# PWR.net
KiCad netlist of a schematic drawn in Altium Designer
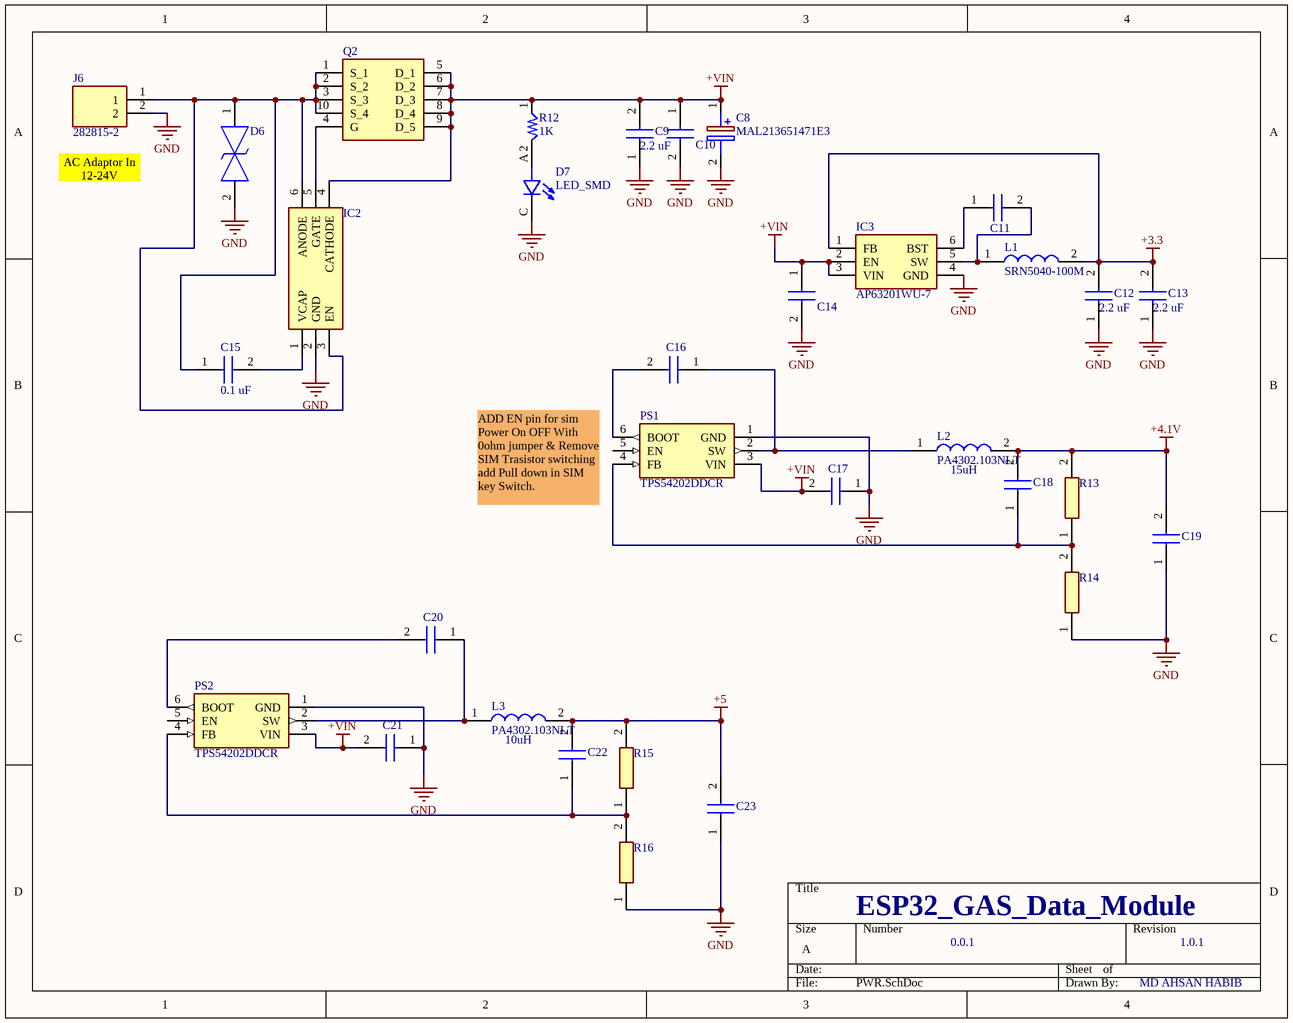
[diagram p0: PWR.SchDoc]

(export (version "E")
  (design (tool "Eeschema 10.0.6"))
  (components
    (comp (ref "C8")
      (value "MAL213651471E3")
      (footprint "CAPPRD500W60D1300H2700")
      (description "Capacitor Polarised")
      (fields (field (name "MOUSER PART NUMBER") "594-2222-136-51471"))
      (libsource (lib "Valve_Controller_Lib") (part "MAL213651471E3"))
    )
    (comp (ref "C9")
      (value "2.2 uF")
      (footprint "CAP0603")
      (description "Capacitor")
      (fields
        (field (name "MANUFACTURER_PART_NUMBER") "CC0603KRX7R9BB104")
        (field (name "MOUSER PART NUMBER") "603-CC603KRX7R9BB104")
      )
      (libsource (lib "Valve_Controller_Lib") (part "CC0603KRX7R9BB104"))
    )
    (comp (ref "C10")
      (value "C5750X5R1H106K230KA")
      (footprint "C5750_Commercial")
      (description "Capacitor")
      (fields (field (name "MOUSER PART NUMBER") "810-C5750X5R1H106K"))
      (libsource (lib "Valve_Controller_Lib") (part "C5750X5R1H106K230KA"))
    )
    (comp (ref "C11")
      (value "C0805C104M5RAC-TU")
      (footprint "CAP0603")
      (description "Capacitor")
      (libsource (lib "Valve_Controller_Lib") (part "C0805C104M5RAC-TU"))
    )
    (comp (ref "C12")
      (value "2.2 uF")
      (footprint "CAP0603")
      (description "Capacitor")
      (fields
        (field (name "MANUFACTURER_PART_NUMBER") "CC0603KRX7R9BB104")
        (field (name "MOUSER PART NUMBER") "603-CC603KRX7R9BB104")
      )
      (libsource (lib "Valve_Controller_Lib") (part "CC0603KRX7R9BB104"))
    )
    (comp (ref "C13")
      (value "2.2 uF")
      (footprint "CAP0603")
      (description "Capacitor")
      (fields
        (field (name "MANUFACTURER_PART_NUMBER") "CC0603KRX7R9BB104")
        (field (name "MOUSER PART NUMBER") "603-CC603KRX7R9BB104")
      )
      (libsource (lib "Valve_Controller_Lib") (part "CC0603KRX7R9BB104"))
    )
    (comp (ref "C14")
      (value "C5750X5R1H106K230KA")
      (footprint "CAP0603")
      (description "Capacitor")
      (fields (field (name "MOUSER PART NUMBER") "810-C5750X5R1H106K"))
      (libsource (lib "Valve_Controller_Lib") (part "C5750X5R1H106K230KA"))
    )
    (comp (ref "C15")
      (value "0.1 uF")
      (footprint "CAP0603")
      (description "Capacitor")
      (fields
        (field (name "MANUFACTURER_PART_NUMBER") "CC0603KRX7R9BB104")
        (field (name "MOUSER PART NUMBER") "603-CC603KRX7R9BB104")
      )
      (libsource (lib "Valve_Controller_Lib") (part "CC0603KRX7R9BB104"))
    )
    (comp (ref "C16")
      (value "C0805C104M5RAC-TU")
      (footprint "CAPC2012X88N")
      (description "Capacitor")
      (libsource (lib "Valve_Controller_Lib") (part "C0805C104M5RAC-TU"))
    )
    (comp (ref "C17")
      (value "C5750X5R1H106K230KA")
      (footprint "CAP0603")
      (description "Capacitor")
      (fields (field (name "MOUSER PART NUMBER") "810-C5750X5R1H106K"))
      (libsource (lib "Valve_Controller_Lib") (part "C5750X5R1H106K230KA"))
    )
    (comp (ref "C18")
      (value "GRM0335C1E560JA01D")
      (footprint "CAP0603")
      (description "Capacitor")
      (fields (field (name "MOUSER PART NUMBER") "81-GRM0335C1E560JA1D"))
      (libsource (lib "Valve_Controller_Lib") (part "GRM0335C1E560JA01D"))
    )
    (comp (ref "C19")
      (value "GRM32ER61C476KE15L")
      (footprint "CAPC3225X270N")
      (description "Capacitor")
      (fields (field (name "MOUSER PART NUMBER") "81-GRM32ER61C476KE5L"))
      (libsource (lib "Valve_Controller_Lib") (part "GRM32ER61C476KE15L"))
    )
    (comp (ref "C20")
      (value "C0805C104M5RAC-TU")
      (footprint "CAPC2012X88N")
      (description "Capacitor")
      (libsource (lib "Valve_Controller_Lib") (part "C0805C104M5RAC-TU"))
    )
    (comp (ref "C21")
      (value "C5750X5R1H106K230KA")
      (footprint "CAP0603")
      (description "Capacitor")
      (fields (field (name "MOUSER PART NUMBER") "810-C5750X5R1H106K"))
      (libsource (lib "Valve_Controller_Lib") (part "C5750X5R1H106K230KA"))
    )
    (comp (ref "C22")
      (value "CGA1A2C0G1E820J030BA")
      (footprint "CAP0603")
      (description "Capacitor")
      (libsource (lib "*") (part "CGA1A2C0G1E820J030BA"))
    )
    (comp (ref "C23")
      (value "GRM32ER61C476KE15L")
      (footprint "CAPC3225X270N")
      (description "Capacitor")
      (fields (field (name "MOUSER PART NUMBER") "81-GRM32ER61C476KE5L"))
      (libsource (lib "Valve_Controller_Lib") (part "GRM32ER61C476KE15L"))
    )
    (comp (ref "D6")
      (value "SMBJ24CA-13-F")
      (footprint "SamacSys:DIONM5336X250N")
      (description "TVS Diode (Bi-directional)")
      (fields (field (name "MOUSER PART NUMBER") "621-SMBJ24CA-13-F"))
      (libsource (lib "*") (part "SMBJ24CA-13-F"))
    )
    (comp (ref "D7")
      (value "LED_SMD")
      (footprint "LEDSC125X200X90-2N")
      (description "Red 633nm LED Indication - Discrete 2.1V 0805 (2012 Metric)")
      (fields (field (name "MF") "Dialight") (field (name "MP") "599-0110-007F"))
      (libsource (lib "Valve_Controller_Lib") (part "5990110007F"))
    )
    (comp (ref "IC2")
      (value "LM74700QDBVTQ1")
      (footprint "SamacSys:SOT95P280X145-6N")
      (description "Integrated Circuit")
      (fields (field (name "MANUFACTURER_PART_NUMBER") "LM74700-Q1MKX-1/NOPB"))
      (libsource (lib "*") (part "LM74700-Q1MKX-1_NOPB"))
    )
    (comp (ref "IC3")
      (value "AP63201WU-7")
      (footprint "SamacSys:SOT95P280X100-6N")
      (description "Integrated Circuit")
      (fields (field (name "MOUSER PART NUMBER") "621-AP63201WU-7"))
      (libsource (lib "*") (part "AP63201WU-7"))
    )
    (comp (ref "J6")
      (value "282815-2")
      (footprint "SamacSys:SHDRRA2W102P0X508_1X2_1016X1200X850P")
      (description "Connector")
      (fields (field (name "MOUSER PART NUMBER") "571-282815-2"))
      (libsource (lib "*") (part "282815-2"))
    )
    (comp (ref "L1")
      (value "SRN5040-100M")
      (footprint "SamacSys:SRN5040")
      (description "Inductor")
      (fields (field (name "MOUSER PART NUMBER") "652-SRN5040-100M"))
      (libsource (lib "*") (part "SRN5040-100M"))
    )
    (comp (ref "L2")
      (value "PA4302.103NLT")
      (footprint "SamacSys:PA4302103NLT")
      (description "Inductor")
      (fields (field (name "MOUSER PART NUMBER") "673-PA4302.103NLT"))
      (libsource (lib "*") (part "PA4302.103NLT"))
    )
    (comp (ref "L3")
      (value "PA4302.103NLT")
      (footprint "SamacSys:PA4302103NLT")
      (description "Inductor")
      (fields (field (name "MOUSER PART NUMBER") "673-PA4302.103NLT"))
      (libsource (lib "*") (part "PA4302.103NLT"))
    )
    (comp (ref "PS1")
      (value "TPS54202DDCR")
      (footprint "SOT95P280X110-6N")
      (description "Power Supply")
      (fields (field (name "MOUSER PART NUMBER") "595-TPS54202DDCR"))
      (libsource (lib "Valve_Controller_Lib") (part "TPS54202DDCR"))
    )
    (comp (ref "PS2")
      (value "TPS54202DDCR")
      (footprint "SOT95P280X110-6N")
      (description "Power Supply")
      (fields (field (name "MOUSER PART NUMBER") "595-TPS54202DDCR"))
      (libsource (lib "Valve_Controller_Lib") (part "TPS54202DDCR"))
    )
    (comp (ref "Q2")
      (value "BSC014N06NSATMA1")
      (footprint "BSC010N04LS6ATMA1")
      (description "MOSFET (N-Channel)")
      (fields (field (name "MOUSER PART NUMBER") "726-BSC014N06NSATMA1"))
      (libsource (lib "Valve_Controller_Lib") (part "BSC014N06NSATMA1"))
    )
    (comp (ref "R12")
      (value "1K")
      (footprint "RES0603")
      (description "Resistor")
      (fields (field (name "MANUFACTURER_PART_NUMBER") "0603WAF1001T5E"))
      (libsource (lib "Valve_Controller_Lib") (part "RES"))
    )
    (comp (ref "R13")
      (value "CRCW0402100KFKEDHP")
      (footprint "RES0603")
      (description "Resistor")
      (fields (field (name "MOUSER PART NUMBER") "71-CRCW0402100KFKEDH"))
      (libsource (lib "Valve_Controller_Lib") (part "CRCW0402100KFKEDHP"))
    )
    (comp (ref "R14")
      (value "CRCW040216K9FKEDHP")
      (footprint "RES0603")
      (description "Resistor")
      (fields (field (name "MOUSER PART NUMBER") "71-CRCW040216K9FKEDH"))
      (libsource (lib "Valve_Controller_Lib") (part "CRCW040216K9FKEDHP"))
    )
    (comp (ref "R15")
      (value "CRCW0402100KFKEDHP")
      (footprint "RES0603")
      (description "Resistor")
      (fields (field (name "MOUSER PART NUMBER") "71-CRCW0402100KFKEDH"))
      (libsource (lib "Valve_Controller_Lib") (part "CRCW0402100KFKEDHP"))
    )
    (comp (ref "R16")
      (value "CRCW040213K7FKEDHP")
      (footprint "RES0603")
      (description "Resistor")
      (libsource (lib "*") (part "CRCW040213K7FKEDHP"))
    )
  )
  (nets
    (net (code "1") (name "+3.3") (class "Default")
      (node (ref "C12") (pin "2") (pinfunction "2_2") (pintype "passive"))
      (node (ref "C13") (pin "2") (pinfunction "2_2") (pintype "passive"))
      (node (ref "IC3") (pin "1") (pinfunction "FB_1") (pintype "passive"))
      (node (ref "L1") (pin "2") (pinfunction "2_2") (pintype "passive"))
    )
    (net (code "2") (name "+4.1V") (class "Default")
      (node (ref "C18") (pin "2") (pinfunction "2_2") (pintype "passive"))
      (node (ref "C19") (pin "2") (pinfunction "2_2") (pintype "passive"))
      (node (ref "L2") (pin "2") (pinfunction "2_2") (pintype "passive"))
      (node (ref "R13") (pin "2") (pinfunction "2_2") (pintype "passive"))
    )
    (net (code "3") (name "+5") (class "Default")
      (node (ref "C22") (pin "2") (pinfunction "2_2") (pintype "passive"))
      (node (ref "C23") (pin "2") (pinfunction "2_2") (pintype "passive"))
      (node (ref "L3") (pin "2") (pinfunction "2_2") (pintype "passive"))
      (node (ref "R15") (pin "2") (pinfunction "2_2") (pintype "passive"))
    )
    (net (code "4") (name "+VIN") (class "Default")
      (node (ref "C10") (pin "1") (pinfunction "1_1") (pintype "passive"))
      (node (ref "C14") (pin "1") (pinfunction "1_1") (pintype "passive"))
      (node (ref "C17") (pin "2") (pinfunction "2_2") (pintype "passive"))
      (node (ref "C21") (pin "2") (pinfunction "2_2") (pintype "passive"))
      (node (ref "C8") (pin "1") (pinfunction "+_1") (pintype "passive"))
      (node (ref "C9") (pin "2") (pinfunction "2_2") (pintype "passive"))
      (node (ref "IC2") (pin "4") (pinfunction "CATHODE_4") (pintype "passive"))
      (node (ref "IC3") (pin "2") (pinfunction "EN_2") (pintype "passive"))
      (node (ref "IC3") (pin "3") (pinfunction "VIN_3") (pintype "passive"))
      (node (ref "PS1") (pin "3") (pinfunction "VIN_3") (pintype "power_in"))
      (node (ref "PS2") (pin "3") (pinfunction "VIN_3") (pintype "power_in"))
      (node (ref "Q2") (pin "5") (pinfunction "D_1_5") (pintype "passive"))
      (node (ref "Q2") (pin "6") (pinfunction "D_2_6") (pintype "passive"))
      (node (ref "Q2") (pin "7") (pinfunction "D_3_7") (pintype "passive"))
      (node (ref "Q2") (pin "8") (pinfunction "D_4_8") (pintype "passive"))
      (node (ref "Q2") (pin "9") (pinfunction "D_5_9") (pintype "passive"))
      (node (ref "R12") (pin "1") (pinfunction "1_1") (pintype "passive"))
    )
    (net (code "5") (name "GND") (class "Default")
      (node (ref "C10") (pin "2") (pinfunction "2_2") (pintype "passive"))
      (node (ref "C12") (pin "1") (pinfunction "1_1") (pintype "passive"))
      (node (ref "C13") (pin "1") (pinfunction "1_1") (pintype "passive"))
      (node (ref "C14") (pin "2") (pinfunction "2_2") (pintype "passive"))
      (node (ref "C17") (pin "1") (pinfunction "1_1") (pintype "passive"))
      (node (ref "C19") (pin "1") (pinfunction "1_1") (pintype "passive"))
      (node (ref "C21") (pin "1") (pinfunction "1_1") (pintype "passive"))
      (node (ref "C23") (pin "1") (pinfunction "1_1") (pintype "passive"))
      (node (ref "C8") (pin "2") (pinfunction "-_2") (pintype "passive"))
      (node (ref "C9") (pin "1") (pinfunction "1_1") (pintype "passive"))
      (node (ref "D6") (pin "2") (pinfunction "2_2") (pintype "passive"))
      (node (ref "D7") (pin "C") (pinfunction "C_C") (pintype "passive"))
      (node (ref "IC2") (pin "2") (pinfunction "GND_2") (pintype "passive"))
      (node (ref "IC3") (pin "4") (pinfunction "GND_4") (pintype "passive"))
      (node (ref "J6") (pin "2") (pinfunction "2_2") (pintype "passive"))
      (node (ref "PS1") (pin "1") (pinfunction "GND_1") (pintype "power_in"))
      (node (ref "PS2") (pin "1") (pinfunction "GND_1") (pintype "power_in"))
      (node (ref "R14") (pin "1") (pinfunction "1_1") (pintype "passive"))
      (node (ref "R16") (pin "1") (pinfunction "1_1") (pintype "passive"))
    )
    (net (code "6") (name "Net-(D7-PadA)") (class "Default")
      (node (ref "D7") (pin "A") (pinfunction "A_A") (pintype "passive"))
      (node (ref "R12") (pin "2") (pinfunction "2_2") (pintype "passive"))
    )
    (net (code "7") (name "Net-(IC2-ANODE)") (class "Default")
      (node (ref "C15") (pin "1") (pinfunction "1_1") (pintype "passive"))
      (node (ref "D6") (pin "1") (pinfunction "1_1") (pintype "passive"))
      (node (ref "IC2") (pin "3") (pinfunction "EN_3") (pintype "passive"))
      (node (ref "IC2") (pin "6") (pinfunction "ANODE_6") (pintype "passive"))
      (node (ref "J6") (pin "1") (pinfunction "1_1") (pintype "passive"))
      (node (ref "Q2") (pin "1") (pinfunction "S_1_1") (pintype "passive"))
      (node (ref "Q2") (pin "10") (pinfunction "S_4_10") (pintype "passive"))
      (node (ref "Q2") (pin "2") (pinfunction "S_2_2") (pintype "passive"))
      (node (ref "Q2") (pin "3") (pinfunction "S_3_3") (pintype "passive"))
    )
    (net (code "8") (name "Net-(IC2-GATE)") (class "Default")
      (node (ref "IC2") (pin "5") (pinfunction "GATE_5") (pintype "passive"))
      (node (ref "Q2") (pin "4") (pinfunction "G_4") (pintype "passive"))
    )
    (net (code "9") (name "Net-(IC2-VCAP)") (class "Default")
      (node (ref "C15") (pin "2") (pinfunction "2_2") (pintype "passive"))
      (node (ref "IC2") (pin "1") (pinfunction "VCAP_1") (pintype "passive"))
    )
    (net (code "10") (name "Net-(IC3-BST)") (class "Default")
      (node (ref "C11") (pin "1") (pinfunction "1_1") (pintype "passive"))
      (node (ref "IC3") (pin "6") (pinfunction "BST_6") (pintype "passive"))
    )
    (net (code "11") (name "Net-(IC3-SW)") (class "Default")
      (node (ref "C11") (pin "2") (pinfunction "2_2") (pintype "passive"))
      (node (ref "IC3") (pin "5") (pinfunction "SW_5") (pintype "passive"))
      (node (ref "L1") (pin "1") (pinfunction "1_1") (pintype "passive"))
    )
    (net (code "12") (name "Net-(PS1-BOOT)") (class "Default")
      (node (ref "C16") (pin "2") (pinfunction "2_2") (pintype "passive"))
      (node (ref "PS1") (pin "6") (pinfunction "BOOT_6") (pintype "output"))
    )
    (net (code "13") (name "Net-(PS1-FB)") (class "Default")
      (node (ref "C18") (pin "1") (pinfunction "1_1") (pintype "passive"))
      (node (ref "PS1") (pin "4") (pinfunction "FB_4") (pintype "input"))
      (node (ref "R13") (pin "1") (pinfunction "1_1") (pintype "passive"))
      (node (ref "R14") (pin "2") (pinfunction "2_2") (pintype "passive"))
    )
    (net (code "14") (name "Net-(PS1-SW)") (class "Default")
      (node (ref "C16") (pin "1") (pinfunction "1_1") (pintype "passive"))
      (node (ref "L2") (pin "1") (pinfunction "1_1") (pintype "passive"))
      (node (ref "PS1") (pin "2") (pinfunction "SW_2") (pintype "output"))
    )
    (net (code "15") (name "Net-(PS2-BOOT)") (class "Default")
      (node (ref "C20") (pin "2") (pinfunction "2_2") (pintype "passive"))
      (node (ref "PS2") (pin "6") (pinfunction "BOOT_6") (pintype "output"))
    )
    (net (code "16") (name "Net-(PS2-FB)") (class "Default")
      (node (ref "C22") (pin "1") (pinfunction "1_1") (pintype "passive"))
      (node (ref "PS2") (pin "4") (pinfunction "FB_4") (pintype "input"))
      (node (ref "R15") (pin "1") (pinfunction "1_1") (pintype "passive"))
      (node (ref "R16") (pin "2") (pinfunction "2_2") (pintype "passive"))
    )
    (net (code "17") (name "Net-(PS2-SW)") (class "Default")
      (node (ref "C20") (pin "1") (pinfunction "1_1") (pintype "passive"))
      (node (ref "L3") (pin "1") (pinfunction "1_1") (pintype "passive"))
      (node (ref "PS2") (pin "2") (pinfunction "SW_2") (pintype "output"))
    )
    (net (code "18") (name "unconnected-(PS1-EN-Pad5)") (class "Default")
      (node (ref "PS1") (pin "5") (pinfunction "EN_5") (pintype "input"))
    )
    (net (code "19") (name "unconnected-(PS2-EN-Pad5)") (class "Default")
      (node (ref "PS2") (pin "5") (pinfunction "EN_5") (pintype "input"))
    )
  )
)
